# I2S_Mic_with_0603_resistors.net
KiCad netlist of a schematic drawn in EAGLE
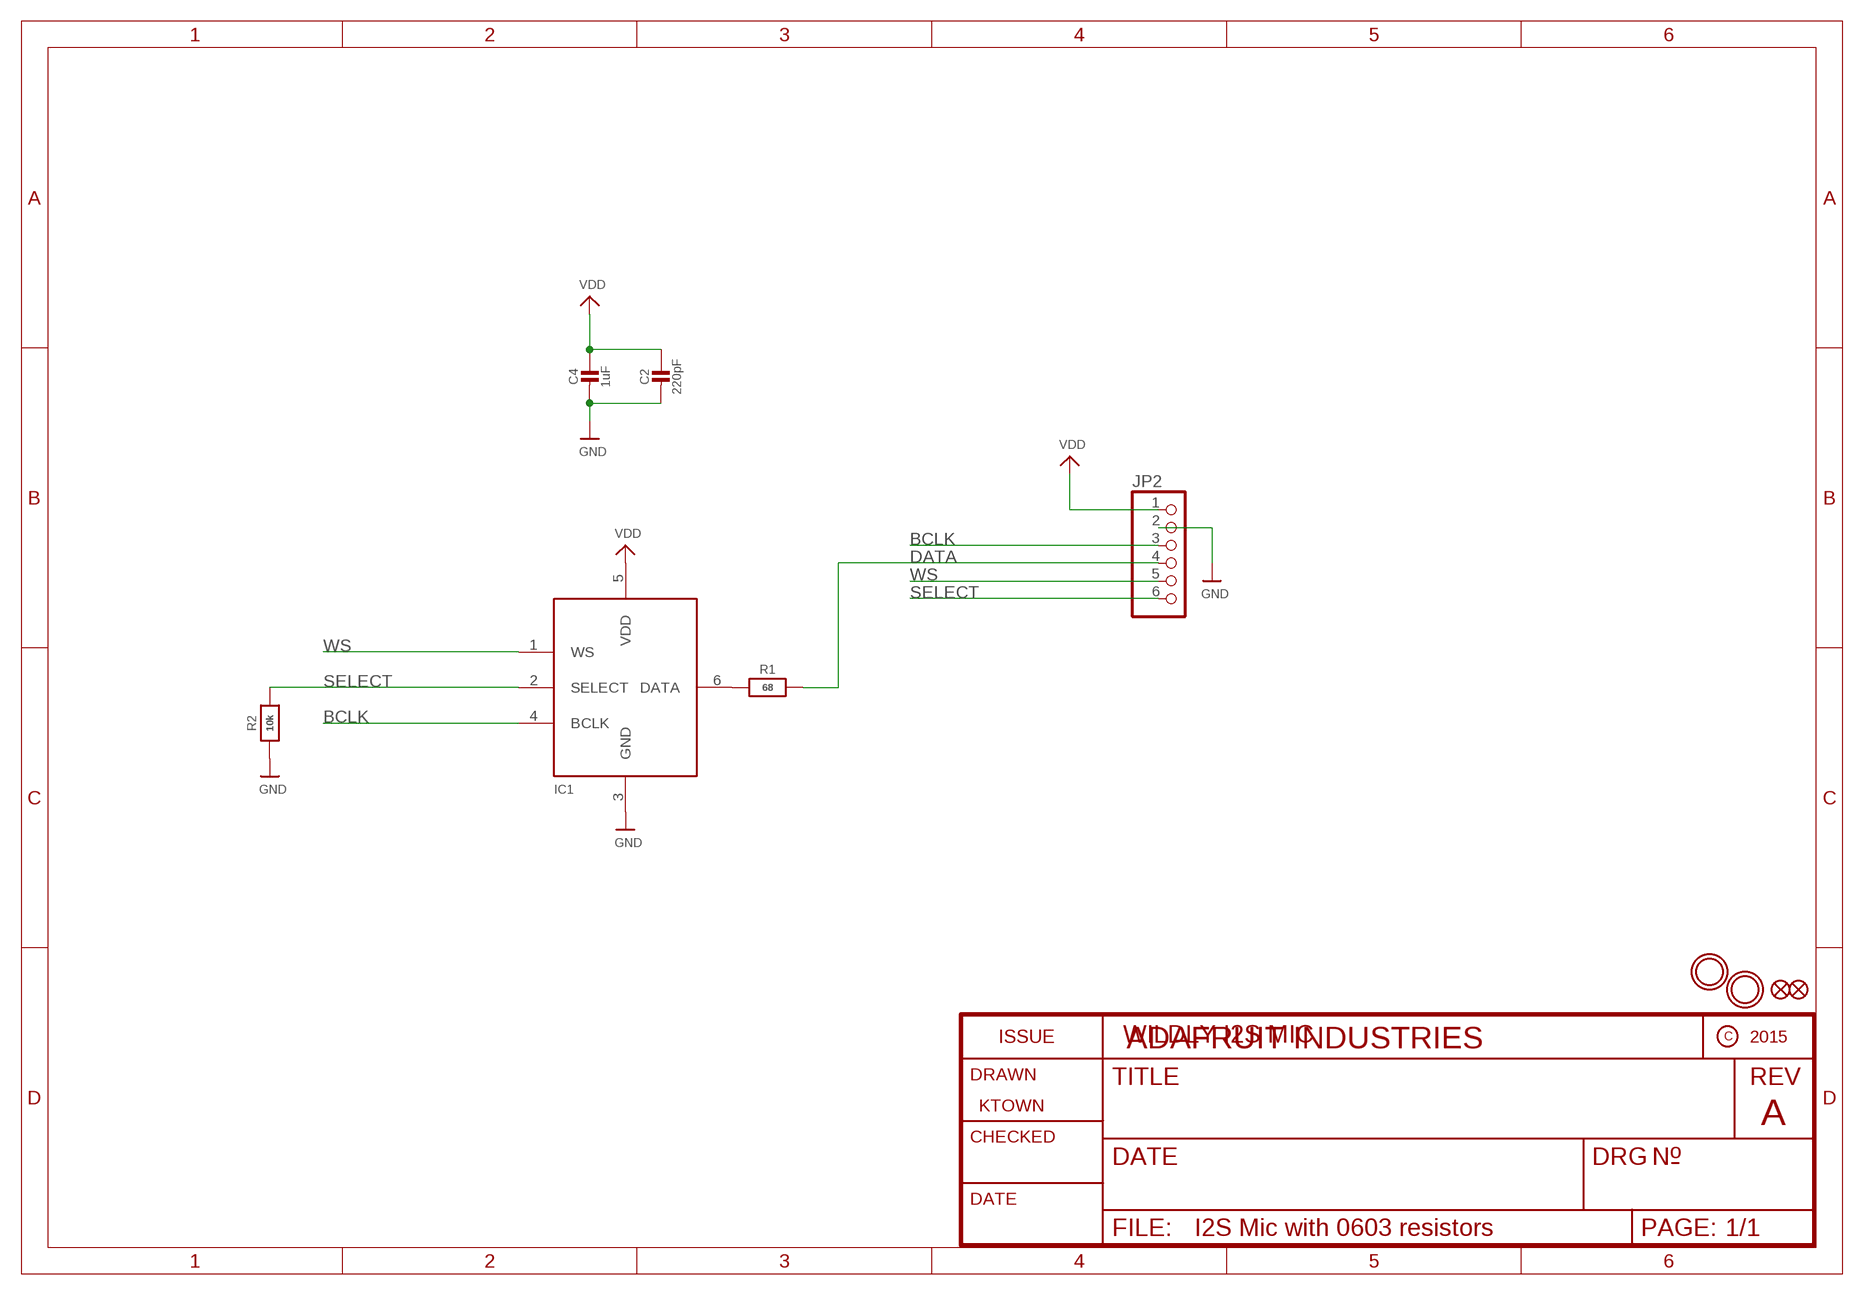
[diagram p0: schematic, sheet 1]

(export (version "E")
  (design (tool "Eeschema 10.0.6"))
  (components
    (comp (ref "C2")
      (value "220pF")
      (footprint "eagle-import:0805-NO")
      (libsource (lib "eagle-import") (part "CAP_CERAMIC0805-NOOUTLINE"))
    )
    (comp (ref "C4")
      (value "1uF")
      (footprint "eagle-import:0805-NO")
      (libsource (lib "eagle-import") (part "CAP_CERAMIC0805-NOOUTLINE"))
    )
    (comp (ref "FID1")
      (value "FIDUCIAL_1MM")
      (footprint "eagle-import:FIDUCIAL_1MM")
      (libsource (lib "eagle-import") (part "FIDUCIAL_1MM"))
    )
    (comp (ref "FID2")
      (value "FIDUCIAL_1MM")
      (footprint "eagle-import:FIDUCIAL_1MM")
      (libsource (lib "eagle-import") (part "FIDUCIAL_1MM"))
    )
    (comp (ref "IC1")
      (value "MIC_I2S_SPH0645")
      (footprint "eagle-import:SPH0645LM4H")
      (libsource (lib "eagle-import") (part "MIC_I2S_SPH0645"))
    )
    (comp (ref "JP2")
      (value "HEADER-1X6ROUND")
      (footprint "eagle-import:1X06_ROUND")
      (libsource (lib "eagle-import") (part "HEADER-1X6ROUND"))
    )
    (comp (ref "R1")
      (value "68")
      (footprint "eagle-import:0603-NO")
      (libsource (lib "eagle-import") (part "RESISTOR_0603_NOOUT"))
    )
    (comp (ref "R2")
      (value "10k")
      (footprint "eagle-import:0603-NO")
      (libsource (lib "eagle-import") (part "RESISTOR_0603_NOOUT"))
    )
    (comp (ref "U$6")
      (value "MOUNTINGHOLE2.5")
      (footprint "eagle-import:MOUNTINGHOLE_2.5_PLATED")
      (libsource (lib "eagle-import") (part "MOUNTINGHOLE2.5"))
    )
    (comp (ref "U$12")
      (value "MOUNTINGHOLE2.5")
      (footprint "eagle-import:MOUNTINGHOLE_2.5_PLATED")
      (libsource (lib "eagle-import") (part "MOUNTINGHOLE2.5"))
    )
  )
  (nets
    (net (code "1") (name "/BCLK") (class "Default")
      (node (ref "IC1") (pin "4") (pinfunction "BCLK_4") (pintype "input"))
      (node (ref "JP2") (pin "3") (pinfunction "3_3") (pintype "passive"))
    )
    (net (code "2") (name "/DATA") (class "Default")
      (node (ref "JP2") (pin "4") (pinfunction "4_4") (pintype "passive"))
      (node (ref "R1") (pin "2") (pinfunction "2_2") (pintype "passive"))
    )
    (net (code "3") (name "/SELECT") (class "Default")
      (node (ref "IC1") (pin "2") (pinfunction "SELECT_2") (pintype "input"))
      (node (ref "JP2") (pin "6") (pinfunction "6_6") (pintype "passive"))
      (node (ref "R2") (pin "2") (pinfunction "2_2") (pintype "passive"))
    )
    (net (code "4") (name "/WS") (class "Default")
      (node (ref "IC1") (pin "1") (pinfunction "WS_1") (pintype "input"))
      (node (ref "JP2") (pin "5") (pinfunction "5_5") (pintype "passive"))
    )
    (net (code "5") (name "GND") (class "Default")
      (node (ref "C2") (pin "2") (pinfunction "2_2") (pintype "passive"))
      (node (ref "C4") (pin "2") (pinfunction "2_2") (pintype "passive"))
      (node (ref "IC1") (pin "3") (pinfunction "GND_3") (pintype "power_in"))
      (node (ref "JP2") (pin "2") (pinfunction "2_2") (pintype "passive"))
      (node (ref "R2") (pin "1") (pinfunction "1_1") (pintype "passive"))
    )
    (net (code "6") (name "Net-(IC1-DATA)") (class "Default")
      (node (ref "IC1") (pin "6") (pinfunction "DATA_6") (pintype "output"))
      (node (ref "R1") (pin "1") (pinfunction "1_1") (pintype "passive"))
    )
    (net (code "7") (name "VDD") (class "Default")
      (node (ref "C2") (pin "1") (pinfunction "1_1") (pintype "passive"))
      (node (ref "C4") (pin "1") (pinfunction "1_1") (pintype "passive"))
      (node (ref "IC1") (pin "5") (pinfunction "VDD_5") (pintype "power_in"))
      (node (ref "JP2") (pin "1") (pinfunction "1_1") (pintype "passive"))
    )
  )
)
